# daplink_stm32f205_test.net
KiCad netlist of a schematic drawn in Altium Designer
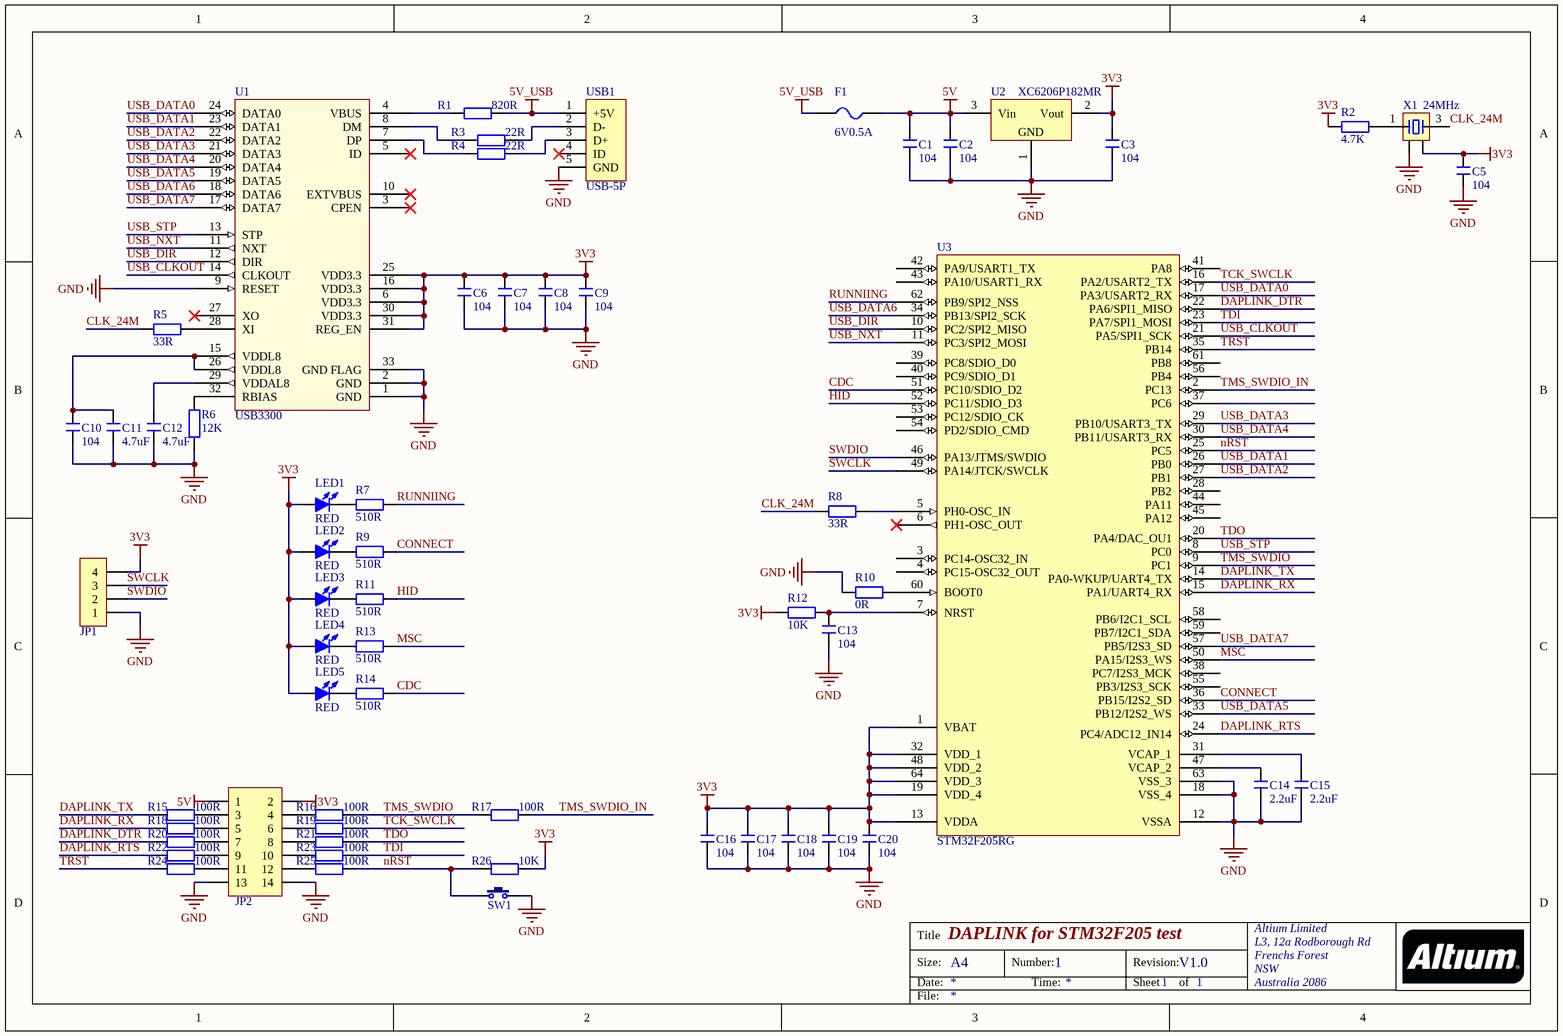
[diagram p0: daplink_stm32f205_test.SchDoc]

(export (version "E")
  (design (tool "Eeschema 10.0.6"))
  (components
    (comp (ref "C1")
      (value "104")
      (footprint "C 0603")
      (description "无极性贴片电容")
      (fields (field (name "版权归属") "源创客"))
      (libsource (lib "daplink") (part "C"))
    )
    (comp (ref "C2")
      (value "104")
      (footprint "C 0805")
      (description "无极性贴片电容")
      (fields (field (name "版权归属") "源创客"))
      (libsource (lib "daplink") (part "C"))
    )
    (comp (ref "C3")
      (value "104")
      (footprint "C 0603")
      (description "无极性贴片电容")
      (fields (field (name "版权归属") "源创客"))
      (libsource (lib "daplink") (part "C"))
    )
    (comp (ref "C5")
      (value "104")
      (footprint "C 0603")
      (description "无极性贴片电容")
      (fields (field (name "版权归属") "源创客"))
      (libsource (lib "daplink") (part "C"))
    )
    (comp (ref "C6")
      (value "104")
      (footprint "C 0603")
      (description "无极性贴片电容")
      (fields (field (name "版权归属") "源创客"))
      (libsource (lib "daplink") (part "C"))
    )
    (comp (ref "C7")
      (value "104")
      (footprint "C 0603")
      (description "无极性贴片电容")
      (fields (field (name "版权归属") "源创客"))
      (libsource (lib "daplink") (part "C"))
    )
    (comp (ref "C8")
      (value "104")
      (footprint "C 0603")
      (description "无极性贴片电容")
      (fields (field (name "版权归属") "源创客"))
      (libsource (lib "daplink") (part "C"))
    )
    (comp (ref "C9")
      (value "104")
      (footprint "C 0603")
      (description "无极性贴片电容")
      (fields (field (name "版权归属") "源创客"))
      (libsource (lib "daplink") (part "C"))
    )
    (comp (ref "C10")
      (value "104")
      (footprint "C 0603")
      (description "无极性贴片电容")
      (fields (field (name "版权归属") "源创客"))
      (libsource (lib "daplink") (part "C"))
    )
    (comp (ref "C11")
      (value "4.7uF")
      (footprint "C 0603")
      (description "无极性贴片电容")
      (fields (field (name "版权归属") "源创客"))
      (libsource (lib "daplink") (part "C"))
    )
    (comp (ref "C12")
      (value "4.7uF")
      (footprint "C 0603")
      (description "无极性贴片电容")
      (fields (field (name "版权归属") "源创客"))
      (libsource (lib "daplink") (part "C"))
    )
    (comp (ref "C13")
      (value "104")
      (footprint "C 0603")
      (description "无极性贴片电容")
      (fields (field (name "版权归属") "源创客"))
      (libsource (lib "daplink") (part "C"))
    )
    (comp (ref "C14")
      (value "2.2uF")
      (footprint "C 0603")
      (description "无极性贴片电容")
      (fields (field (name "版权归属") "源创客"))
      (libsource (lib "daplink") (part "C"))
    )
    (comp (ref "C15")
      (value "2.2uF")
      (footprint "C 0603")
      (description "无极性贴片电容")
      (fields (field (name "版权归属") "源创客"))
      (libsource (lib "daplink") (part "C"))
    )
    (comp (ref "C16")
      (value "104")
      (footprint "C 0603")
      (description "无极性贴片电容")
      (fields (field (name "版权归属") "源创客"))
      (libsource (lib "daplink") (part "C"))
    )
    (comp (ref "C17")
      (value "104")
      (footprint "C 0603")
      (description "无极性贴片电容")
      (fields (field (name "版权归属") "源创客"))
      (libsource (lib "daplink") (part "C"))
    )
    (comp (ref "C18")
      (value "104")
      (footprint "C 0603")
      (description "无极性贴片电容")
      (fields (field (name "版权归属") "源创客"))
      (libsource (lib "daplink") (part "C"))
    )
    (comp (ref "C19")
      (value "104")
      (footprint "C 0603")
      (description "无极性贴片电容")
      (fields (field (name "版权归属") "源创客"))
      (libsource (lib "daplink") (part "C"))
    )
    (comp (ref "C20")
      (value "104")
      (footprint "C 0603")
      (description "无极性贴片电容")
      (fields (field (name "版权归属") "源创客"))
      (libsource (lib "daplink") (part "C"))
    )
    (comp (ref "F1")
      (value "6V0.5A")
      (footprint "FU 0805")
      (description "贴片保险丝")
      (fields (field (name "版权归属") "源创客"))
      (libsource (lib "daplink") (part "FU"))
    )
    (comp (ref "JP1")
      (value "HDR-1X4")
      (footprint "HDR-1X4")
      (description "4P接插件")
      (fields (field (name "版权归属") "源创客"))
      (libsource (lib "daplink") (part "Header 4"))
    )
    (comp (ref "JP2")
      (value "Header 2X7")
      (footprint "HDR-7X2_H")
      (description "7*2P接插件")
      (fields (field (name "版权归属") "源创客"))
      (libsource (lib "接插件") (part "Header 7X2"))
    )
    (comp (ref "LED1")
      (value "RED")
      (footprint "LED 0805B")
      (description "贴片LED")
      (fields (field (name "版权归属") "源创客"))
      (libsource (lib "daplink") (part "LED-SMD"))
    )
    (comp (ref "LED2")
      (value "RED")
      (footprint "LED 0805B")
      (description "贴片LED")
      (fields (field (name "版权归属") "源创客"))
      (libsource (lib "daplink") (part "LED-SMD"))
    )
    (comp (ref "LED3")
      (value "RED")
      (footprint "LED 0805B")
      (description "贴片LED")
      (fields (field (name "版权归属") "源创客"))
      (libsource (lib "daplink") (part "LED-SMD"))
    )
    (comp (ref "LED4")
      (value "RED")
      (footprint "LED 0805B")
      (description "贴片LED")
      (fields (field (name "版权归属") "源创客"))
      (libsource (lib "daplink") (part "LED-SMD"))
    )
    (comp (ref "LED5")
      (value "RED")
      (footprint "LED 0805B")
      (description "贴片LED")
      (fields (field (name "版权归属") "源创客"))
      (libsource (lib "daplink") (part "LED-SMD"))
    )
    (comp (ref "R1")
      (value "820R")
      (footprint "R 0603")
      (description "贴片电阻")
      (fields (field (name "版权归属") "源创客"))
      (libsource (lib "daplink") (part "R"))
    )
    (comp (ref "R2")
      (value "4.7K")
      (footprint "R 0603")
      (description "贴片电阻")
      (fields (field (name "版权归属") "源创客"))
      (libsource (lib "daplink") (part "R"))
    )
    (comp (ref "R3")
      (value "22R")
      (footprint "R 0603")
      (description "贴片电阻")
      (fields (field (name "版权归属") "源创客"))
      (libsource (lib "daplink") (part "R"))
    )
    (comp (ref "R4")
      (value "22R")
      (footprint "R 0603")
      (description "贴片电阻")
      (fields (field (name "版权归属") "源创客"))
      (libsource (lib "daplink") (part "R"))
    )
    (comp (ref "R5")
      (value "33R")
      (footprint "R 0603")
      (description "贴片电阻")
      (fields (field (name "版权归属") "源创客"))
      (libsource (lib "daplink") (part "R"))
    )
    (comp (ref "R6")
      (value "12K")
      (footprint "R 0603")
      (description "贴片电阻")
      (fields (field (name "版权归属") "源创客"))
      (libsource (lib "daplink") (part "R"))
    )
    (comp (ref "R7")
      (value "510R")
      (footprint "R 0603")
      (description "贴片电阻")
      (fields (field (name "版权归属") "源创客"))
      (libsource (lib "daplink") (part "R"))
    )
    (comp (ref "R8")
      (value "33R")
      (footprint "R 0603")
      (description "贴片电阻")
      (fields (field (name "版权归属") "源创客"))
      (libsource (lib "daplink") (part "R"))
    )
    (comp (ref "R9")
      (value "510R")
      (footprint "R 0603")
      (description "贴片电阻")
      (fields (field (name "版权归属") "源创客"))
      (libsource (lib "daplink") (part "R"))
    )
    (comp (ref "R10")
      (value "0R")
      (footprint "R 0603")
      (description "贴片电阻")
      (fields (field (name "版权归属") "源创客"))
      (libsource (lib "daplink") (part "R"))
    )
    (comp (ref "R11")
      (value "510R")
      (footprint "R 0603")
      (description "贴片电阻")
      (fields (field (name "版权归属") "源创客"))
      (libsource (lib "daplink") (part "R"))
    )
    (comp (ref "R12")
      (value "10K")
      (footprint "R 0603")
      (description "贴片电阻")
      (fields (field (name "版权归属") "源创客"))
      (libsource (lib "daplink") (part "R"))
    )
    (comp (ref "R13")
      (value "510R")
      (footprint "R 0603")
      (description "贴片电阻")
      (fields (field (name "版权归属") "源创客"))
      (libsource (lib "daplink") (part "R"))
    )
    (comp (ref "R14")
      (value "510R")
      (footprint "R 0603")
      (description "贴片电阻")
      (fields (field (name "版权归属") "源创客"))
      (libsource (lib "daplink") (part "R"))
    )
    (comp (ref "R15")
      (value "100R")
      (footprint "R 0603")
      (description "贴片电阻")
      (fields (field (name "版权归属") "源创客"))
      (libsource (lib "daplink") (part "R"))
    )
    (comp (ref "R16")
      (value "100R")
      (footprint "R 0603")
      (description "贴片电阻")
      (fields (field (name "版权归属") "源创客"))
      (libsource (lib "daplink") (part "R"))
    )
    (comp (ref "R17")
      (value "100R")
      (footprint "R 0603")
      (description "贴片电阻")
      (fields (field (name "版权归属") "源创客"))
      (libsource (lib "daplink") (part "R"))
    )
    (comp (ref "R18")
      (value "100R")
      (footprint "R 0603")
      (description "贴片电阻")
      (fields (field (name "版权归属") "源创客"))
      (libsource (lib "daplink") (part "R"))
    )
    (comp (ref "R19")
      (value "100R")
      (footprint "R 0603")
      (description "贴片电阻")
      (fields (field (name "版权归属") "源创客"))
      (libsource (lib "daplink") (part "R"))
    )
    (comp (ref "R20")
      (value "100R")
      (footprint "R 0603")
      (description "贴片电阻")
      (fields (field (name "版权归属") "源创客"))
      (libsource (lib "daplink") (part "R"))
    )
    (comp (ref "R21")
      (value "100R")
      (footprint "R 0603")
      (description "贴片电阻")
      (fields (field (name "版权归属") "源创客"))
      (libsource (lib "daplink") (part "R"))
    )
    (comp (ref "R22")
      (value "100R")
      (footprint "R 0603")
      (description "贴片电阻")
      (fields (field (name "版权归属") "源创客"))
      (libsource (lib "daplink") (part "R"))
    )
    (comp (ref "R23")
      (value "100R")
      (footprint "R 0603")
      (description "贴片电阻")
      (fields (field (name "版权归属") "源创客"))
      (libsource (lib "daplink") (part "R"))
    )
    (comp (ref "R24")
      (value "100R")
      (footprint "R 0603")
      (description "贴片电阻")
      (fields (field (name "版权归属") "源创客"))
      (libsource (lib "daplink") (part "R"))
    )
    (comp (ref "R25")
      (value "100R")
      (footprint "R 0603")
      (description "贴片电阻")
      (fields (field (name "版权归属") "源创客"))
      (libsource (lib "daplink") (part "R"))
    )
    (comp (ref "R26")
      (value "10K")
      (footprint "R 0603")
      (description "贴片电阻")
      (fields (field (name "版权归属") "源创客"))
      (libsource (lib "daplink") (part "R"))
    )
    (comp (ref "SW1")
      (value "3x6x5")
      (footprint "TSW 3*6*4.3-S-W")
      (description "3x6轻触开关")
      (fields (field (name "版权归属") "源创客"))
      (libsource (lib "按键-开关") (part "TSW 3x6"))
    )
    (comp (ref "U1")
      (value "USB3300")
      (footprint "QFN32 5x5_N")
      (description "USB PHY")
      (libsource (lib "daplink") (part "USB3300"))
    )
    (comp (ref "U2")
      (value "XC6206P182MR")
      (footprint "SOT23-3N")
      (description "三端稳压芯片")
      (libsource (lib "daplink") (part "XC6206P182MR"))
    )
    (comp (ref "U3")
      (value "STM32F205RG")
      (footprint "LQFP64 10X10_N")
      (description "32位STM单片机")
      (fields (field (name "版权归属") "源创客"))
      (libsource (lib "daplink") (part "STM32F205RG"))
    )
    (comp (ref "USB1")
      (value "USB-5P")
      (footprint "micro usb")
      (description "微型USB母座")
      (fields (field (name "版权归属") "源创客"))
      (libsource (lib "daplink") (part "USB-5P"))
    )
    (comp (ref "X1")
      (value "24MHz")
      (footprint "XTAL-5032")
      (description "4脚晶振")
      (fields (field (name "版权归属") "源创客"))
      (libsource (lib "daplink") (part "XTAL-4"))
    )
  )
  (nets
    (net (code "1") (name "/CDC") (class "Default")
      (node (ref "R14") (pin "1") (pinfunction "1_1") (pintype "passive"))
      (node (ref "U3") (pin "51") (pinfunction "PC10/SDIO_D2_51") (pintype "bidirectional"))
    )
    (net (code "2") (name "/CLK_24M") (class "Default")
      (node (ref "R5") (pin "1") (pinfunction "1_1") (pintype "passive"))
      (node (ref "R8") (pin "1") (pinfunction "1_1") (pintype "passive"))
      (node (ref "X1") (pin "3") (pinfunction "3_3") (pintype "passive"))
    )
    (net (code "3") (name "/CONNECT") (class "Default")
      (node (ref "R9") (pin "1") (pinfunction "1_1") (pintype "passive"))
      (node (ref "U3") (pin "36") (pinfunction "PB15/I2S2_SD_36") (pintype "bidirectional"))
    )
    (net (code "4") (name "/DAPLINK_DTR") (class "Default")
      (node (ref "R20") (pin "1") (pinfunction "1_1") (pintype "passive"))
      (node (ref "U3") (pin "22") (pinfunction "PA6/SPI1_MISO_22") (pintype "bidirectional"))
    )
    (net (code "5") (name "/DAPLINK_RTS") (class "Default")
      (node (ref "R22") (pin "1") (pinfunction "1_1") (pintype "passive"))
      (node (ref "U3") (pin "24") (pinfunction "PC4/ADC12_IN14_24") (pintype "bidirectional"))
    )
    (net (code "6") (name "/DAPLINK_RX") (class "Default")
      (node (ref "R18") (pin "1") (pinfunction "1_1") (pintype "passive"))
      (node (ref "U3") (pin "15") (pinfunction "PA1/UART4_RX_15") (pintype "bidirectional"))
    )
    (net (code "7") (name "/DAPLINK_TX") (class "Default")
      (node (ref "R15") (pin "1") (pinfunction "1_1") (pintype "passive"))
      (node (ref "U3") (pin "14") (pinfunction "PA0-WKUP/UART4_TX_14") (pintype "bidirectional"))
    )
    (net (code "8") (name "/HID") (class "Default")
      (node (ref "R11") (pin "1") (pinfunction "1_1") (pintype "passive"))
      (node (ref "U3") (pin "52") (pinfunction "PC11/SDIO_D3_52") (pintype "bidirectional"))
    )
    (net (code "9") (name "/MSC") (class "Default")
      (node (ref "R13") (pin "1") (pinfunction "1_1") (pintype "passive"))
      (node (ref "U3") (pin "50") (pinfunction "PA15/I2S3_WS_50") (pintype "bidirectional"))
    )
    (net (code "10") (name "/RUNNIING") (class "Default")
      (node (ref "R7") (pin "1") (pinfunction "1_1") (pintype "passive"))
      (node (ref "U3") (pin "62") (pinfunction "PB9/SPI2_NSS_62") (pintype "bidirectional"))
    )
    (net (code "11") (name "/SWCLK") (class "Default")
      (node (ref "JP1") (pin "3") (pinfunction "3_3") (pintype "passive"))
      (node (ref "U3") (pin "49") (pinfunction "PA14/JTCK/SWCLK_49") (pintype "bidirectional"))
    )
    (net (code "12") (name "/SWDIO") (class "Default")
      (node (ref "JP1") (pin "2") (pinfunction "2_2") (pintype "passive"))
      (node (ref "U3") (pin "46") (pinfunction "PA13/JTMS/SWDIO_46") (pintype "bidirectional"))
    )
    (net (code "13") (name "/TCK_SWCLK") (class "Default")
      (node (ref "R19") (pin "2") (pinfunction "2_2") (pintype "passive"))
      (node (ref "U3") (pin "16") (pinfunction "PA2/USART2_TX_16") (pintype "bidirectional"))
    )
    (net (code "14") (name "/TDI") (class "Default")
      (node (ref "R23") (pin "2") (pinfunction "2_2") (pintype "passive"))
      (node (ref "U3") (pin "23") (pinfunction "PA7/SPI1_MOSI_23") (pintype "bidirectional"))
    )
    (net (code "15") (name "/TDO") (class "Default")
      (node (ref "R21") (pin "2") (pinfunction "2_2") (pintype "passive"))
      (node (ref "U3") (pin "20") (pinfunction "PA4/DAC_OU1_20") (pintype "bidirectional"))
    )
    (net (code "16") (name "/TMS_SWDIO") (class "Default")
      (node (ref "R16") (pin "2") (pinfunction "2_2") (pintype "passive"))
      (node (ref "R17") (pin "1") (pinfunction "1_1") (pintype "passive"))
      (node (ref "U3") (pin "9") (pinfunction "PC1_9") (pintype "bidirectional"))
    )
    (net (code "17") (name "/TMS_SWDIO_IN") (class "Default")
      (node (ref "R17") (pin "2") (pinfunction "2_2") (pintype "passive"))
      (node (ref "U3") (pin "2") (pinfunction "PC13_2") (pintype "bidirectional"))
    )
    (net (code "18") (name "/TRST") (class "Default")
      (node (ref "R24") (pin "1") (pinfunction "1_1") (pintype "passive"))
      (node (ref "U3") (pin "35") (pinfunction "PB14_35") (pintype "bidirectional"))
    )
    (net (code "19") (name "/USB_CLKOUT") (class "Default")
      (node (ref "U1") (pin "14") (pinfunction "CLKOUT_14") (pintype "output"))
      (node (ref "U3") (pin "21") (pinfunction "PA5/SPI1_SCK_21") (pintype "bidirectional"))
    )
    (net (code "20") (name "/USB_DATA0") (class "Default")
      (node (ref "U1") (pin "24") (pinfunction "DATA0_24") (pintype "bidirectional"))
      (node (ref "U3") (pin "17") (pinfunction "PA3/USART2_RX_17") (pintype "bidirectional"))
    )
    (net (code "21") (name "/USB_DATA1") (class "Default")
      (node (ref "U1") (pin "23") (pinfunction "DATA1_23") (pintype "bidirectional"))
      (node (ref "U3") (pin "26") (pinfunction "PB0_26") (pintype "bidirectional"))
    )
    (net (code "22") (name "/USB_DATA2") (class "Default")
      (node (ref "U1") (pin "22") (pinfunction "DATA2_22") (pintype "bidirectional"))
      (node (ref "U3") (pin "27") (pinfunction "PB1_27") (pintype "bidirectional"))
    )
    (net (code "23") (name "/USB_DATA3") (class "Default")
      (node (ref "U1") (pin "21") (pinfunction "DATA3_21") (pintype "bidirectional"))
      (node (ref "U3") (pin "29") (pinfunction "PB10/USART3_TX_29") (pintype "bidirectional"))
    )
    (net (code "24") (name "/USB_DATA4") (class "Default")
      (node (ref "U1") (pin "20") (pinfunction "DATA4_20") (pintype "bidirectional"))
      (node (ref "U3") (pin "30") (pinfunction "PB11/USART3_RX_30") (pintype "bidirectional"))
    )
    (net (code "25") (name "/USB_DATA5") (class "Default")
      (node (ref "U1") (pin "19") (pinfunction "DATA5_19") (pintype "bidirectional"))
      (node (ref "U3") (pin "33") (pinfunction "PB12/I2S2_WS_33") (pintype "bidirectional"))
    )
    (net (code "26") (name "/USB_DATA6") (class "Default")
      (node (ref "U1") (pin "18") (pinfunction "DATA6_18") (pintype "bidirectional"))
      (node (ref "U3") (pin "34") (pinfunction "PB13/SPI2_SCK_34") (pintype "bidirectional"))
    )
    (net (code "27") (name "/USB_DATA7") (class "Default")
      (node (ref "U1") (pin "17") (pinfunction "DATA7_17") (pintype "bidirectional"))
      (node (ref "U3") (pin "57") (pinfunction "PB5/I2S3_SD_57") (pintype "bidirectional"))
    )
    (net (code "28") (name "/USB_DIR") (class "Default")
      (node (ref "U1") (pin "12") (pinfunction "DIR_12") (pintype "output"))
      (node (ref "U3") (pin "10") (pinfunction "PC2/SPI2_MISO_10") (pintype "bidirectional"))
    )
    (net (code "29") (name "/USB_NXT") (class "Default")
      (node (ref "U1") (pin "11") (pinfunction "NXT_11") (pintype "output"))
      (node (ref "U3") (pin "11") (pinfunction "PC3/SPI2_MOSI_11") (pintype "bidirectional"))
    )
    (net (code "30") (name "/USB_STP") (class "Default")
      (node (ref "U1") (pin "13") (pinfunction "STP_13") (pintype "input"))
      (node (ref "U3") (pin "8") (pinfunction "PC0_8") (pintype "bidirectional"))
    )
    (net (code "31") (name "/nRST") (class "Default")
      (node (ref "R25") (pin "2") (pinfunction "2_2") (pintype "passive"))
      (node (ref "R26") (pin "1") (pinfunction "1_1") (pintype "passive"))
      (node (ref "SW1") (pin "1") (pinfunction "1_1") (pintype "passive"))
      (node (ref "U3") (pin "25") (pinfunction "PC5_25") (pintype "bidirectional"))
    )
    (net (code "32") (name "3V3") (class "Default")
      (node (ref "C16") (pin "2") (pinfunction "2_2") (pintype "passive"))
      (node (ref "C17") (pin "2") (pinfunction "2_2") (pintype "passive"))
      (node (ref "C18") (pin "2") (pinfunction "2_2") (pintype "passive"))
      (node (ref "C19") (pin "2") (pinfunction "2_2") (pintype "passive"))
      (node (ref "C20") (pin "2") (pinfunction "2_2") (pintype "passive"))
      (node (ref "C3") (pin "2") (pinfunction "2_2") (pintype "passive"))
      (node (ref "C5") (pin "2") (pinfunction "2_2") (pintype "passive"))
      (node (ref "C6") (pin "2") (pinfunction "2_2") (pintype "passive"))
      (node (ref "C7") (pin "2") (pinfunction "2_2") (pintype "passive"))
      (node (ref "C8") (pin "2") (pinfunction "2_2") (pintype "passive"))
      (node (ref "C9") (pin "2") (pinfunction "2_2") (pintype "passive"))
      (node (ref "JP1") (pin "4") (pinfunction "4_4") (pintype "passive"))
      (node (ref "JP2") (pin "2") (pinfunction "2_2") (pintype "passive"))
      (node (ref "LED1") (pin "1") (pinfunction "A_1") (pintype "passive"))
      (node (ref "LED2") (pin "1") (pinfunction "A_1") (pintype "passive"))
      (node (ref "LED3") (pin "1") (pinfunction "A_1") (pintype "passive"))
      (node (ref "LED4") (pin "1") (pinfunction "A_1") (pintype "passive"))
      (node (ref "LED5") (pin "1") (pinfunction "A_1") (pintype "passive"))
      (node (ref "R12") (pin "1") (pinfunction "1_1") (pintype "passive"))
      (node (ref "R2") (pin "1") (pinfunction "1_1") (pintype "passive"))
      (node (ref "R26") (pin "2") (pinfunction "2_2") (pintype "passive"))
      (node (ref "U1") (pin "16") (pinfunction "VDD3.3_16") (pintype "passive"))
      (node (ref "U1") (pin "25") (pinfunction "VDD3.3_25") (pintype "passive"))
      (node (ref "U1") (pin "30") (pinfunction "VDD3.3_30") (pintype "passive"))
      (node (ref "U1") (pin "31") (pinfunction "REG_EN_31") (pintype "passive"))
      (node (ref "U1") (pin "6") (pinfunction "VDD3.3_6") (pintype "passive"))
      (node (ref "U2") (pin "2") (pinfunction "Vout_2") (pintype "passive"))
      (node (ref "U3") (pin "1") (pinfunction "VBAT_1") (pintype "power_in"))
      (node (ref "U3") (pin "13") (pinfunction "VDDA_13") (pintype "power_in"))
      (node (ref "U3") (pin "19") (pinfunction "VDD_4_19") (pintype "power_in"))
      (node (ref "U3") (pin "32") (pinfunction "VDD_1_32") (pintype "power_in"))
      (node (ref "U3") (pin "48") (pinfunction "VDD_2_48") (pintype "power_in"))
      (node (ref "U3") (pin "64") (pinfunction "VDD_3_64") (pintype "power_in"))
      (node (ref "X1") (pin "4") (pinfunction "4_4") (pintype "passive"))
    )
    (net (code "33") (name "5V") (class "Default")
      (node (ref "C1") (pin "2") (pinfunction "2_2") (pintype "passive"))
      (node (ref "C2") (pin "2") (pinfunction "2_2") (pintype "passive"))
      (node (ref "F1") (pin "2") (pinfunction "2_2") (pintype "passive"))
      (node (ref "JP2") (pin "1") (pinfunction "1_1") (pintype "passive"))
      (node (ref "U2") (pin "3") (pinfunction "Vin_3") (pintype "passive"))
    )
    (net (code "34") (name "5V_USB") (class "Default")
      (node (ref "F1") (pin "1") (pinfunction "1_1") (pintype "passive"))
      (node (ref "R1") (pin "2") (pinfunction "2_2") (pintype "passive"))
      (node (ref "USB1") (pin "1") (pinfunction "+5V_1") (pintype "passive"))
    )
    (net (code "35") (name "GND") (class "Default")
      (node (ref "C1") (pin "1") (pinfunction "1_1") (pintype "passive"))
      (node (ref "C10") (pin "1") (pinfunction "1_1") (pintype "passive"))
      (node (ref "C11") (pin "1") (pinfunction "1_1") (pintype "passive"))
      (node (ref "C12") (pin "1") (pinfunction "1_1") (pintype "passive"))
      (node (ref "C13") (pin "1") (pinfunction "1_1") (pintype "passive"))
      (node (ref "C14") (pin "1") (pinfunction "1_1") (pintype "passive"))
      (node (ref "C15") (pin "1") (pinfunction "1_1") (pintype "passive"))
      (node (ref "C16") (pin "1") (pinfunction "1_1") (pintype "passive"))
      (node (ref "C17") (pin "1") (pinfunction "1_1") (pintype "passive"))
      (node (ref "C18") (pin "1") (pinfunction "1_1") (pintype "passive"))
      (node (ref "C19") (pin "1") (pinfunction "1_1") (pintype "passive"))
      (node (ref "C2") (pin "1") (pinfunction "1_1") (pintype "passive"))
      (node (ref "C20") (pin "1") (pinfunction "1_1") (pintype "passive"))
      (node (ref "C3") (pin "1") (pinfunction "1_1") (pintype "passive"))
      (node (ref "C5") (pin "1") (pinfunction "1_1") (pintype "passive"))
      (node (ref "C6") (pin "1") (pinfunction "1_1") (pintype "passive"))
      (node (ref "C7") (pin "1") (pinfunction "1_1") (pintype "passive"))
      (node (ref "C8") (pin "1") (pinfunction "1_1") (pintype "passive"))
      (node (ref "C9") (pin "1") (pinfunction "1_1") (pintype "passive"))
      (node (ref "JP1") (pin "1") (pinfunction "1_1") (pintype "passive"))
      (node (ref "JP2") (pin "13") (pinfunction "13_13") (pintype "passive"))
      (node (ref "JP2") (pin "14") (pinfunction "14_14") (pintype "passive"))
      (node (ref "R10") (pin "1") (pinfunction "1_1") (pintype "passive"))
      (node (ref "R6") (pin "1") (pinfunction "1_1") (pintype "passive"))
      (node (ref "SW1") (pin "2") (pinfunction "2_2") (pintype "passive"))
      (node (ref "U1") (pin "1") (pinfunction "GND_1") (pintype "passive"))
      (node (ref "U1") (pin "2") (pinfunction "GND_2") (pintype "passive"))
      (node (ref "U1") (pin "33") (pinfunction "GND_FLAG_33") (pintype "passive"))
      (node (ref "U1") (pin "9") (pinfunction "RESET_9") (pintype "input"))
      (node (ref "U2") (pin "1") (pinfunction "GND_1") (pintype "passive"))
      (node (ref "U3") (pin "12") (pinfunction "VSSA_12") (pintype "power_in"))
      (node (ref "U3") (pin "18") (pinfunction "VSS_4_18") (pintype "power_in"))
      (node (ref "U3") (pin "63") (pinfunction "VSS_3_63") (pintype "power_in"))
      (node (ref "USB1") (pin "5") (pinfunction "GND_5") (pintype "passive"))
      (node (ref "X1") (pin "2") (pinfunction "2_2") (pintype "passive"))
    )
    (net (code "36") (name "Net-(C10-Pad2)") (class "Default")
      (node (ref "C10") (pin "2") (pinfunction "2_2") (pintype "passive"))
      (node (ref "C11") (pin "2") (pinfunction "2_2") (pintype "passive"))
      (node (ref "U1") (pin "15") (pinfunction "VDDL8_15") (pintype "output"))
      (node (ref "U1") (pin "26") (pinfunction "VDDL8_26") (pintype "output"))
    )
    (net (code "37") (name "Net-(JP2-Pad3)") (class "Default")
      (node (ref "JP2") (pin "3") (pinfunction "3_3") (pintype "passive"))
      (node (ref "R15") (pin "2") (pinfunction "2_2") (pintype "passive"))
    )
    (net (code "38") (name "Net-(JP2-Pad4)") (class "Default")
      (node (ref "JP2") (pin "4") (pinfunction "4_4") (pintype "passive"))
      (node (ref "R16") (pin "1") (pinfunction "1_1") (pintype "passive"))
    )
    (net (code "39") (name "Net-(JP2-Pad5)") (class "Default")
      (node (ref "JP2") (pin "5") (pinfunction "5_5") (pintype "passive"))
      (node (ref "R18") (pin "2") (pinfunction "2_2") (pintype "passive"))
    )
    (net (code "40") (name "Net-(JP2-Pad6)") (class "Default")
      (node (ref "JP2") (pin "6") (pinfunction "6_6") (pintype "passive"))
      (node (ref "R19") (pin "1") (pinfunction "1_1") (pintype "passive"))
    )
    (net (code "41") (name "Net-(JP2-Pad7)") (class "Default")
      (node (ref "JP2") (pin "7") (pinfunction "7_7") (pintype "passive"))
      (node (ref "R20") (pin "2") (pinfunction "2_2") (pintype "passive"))
    )
    (net (code "42") (name "Net-(JP2-Pad8)") (class "Default")
      (node (ref "JP2") (pin "8") (pinfunction "8_8") (pintype "passive"))
      (node (ref "R21") (pin "1") (pinfunction "1_1") (pintype "passive"))
    )
    (net (code "43") (name "Net-(JP2-Pad9)") (class "Default")
      (node (ref "JP2") (pin "9") (pinfunction "9_9") (pintype "passive"))
      (node (ref "R22") (pin "2") (pinfunction "2_2") (pintype "passive"))
    )
    (net (code "44") (name "Net-(JP2-Pad10)") (class "Default")
      (node (ref "JP2") (pin "10") (pinfunction "10_10") (pintype "passive"))
      (node (ref "R23") (pin "1") (pinfunction "1_1") (pintype "passive"))
    )
    (net (code "45") (name "Net-(JP2-Pad11)") (class "Default")
      (node (ref "JP2") (pin "11") (pinfunction "11_11") (pintype "passive"))
      (node (ref "R24") (pin "2") (pinfunction "2_2") (pintype "passive"))
    )
    (net (code "46") (name "Net-(JP2-Pad12)") (class "Default")
      (node (ref "JP2") (pin "12") (pinfunction "12_12") (pintype "passive"))
      (node (ref "R25") (pin "1") (pinfunction "1_1") (pintype "passive"))
    )
    (net (code "47") (name "Net-(LED1-K)") (class "Default")
      (node (ref "LED1") (pin "2") (pinfunction "K_2") (pintype "passive"))
      (node (ref "R7") (pin "2") (pinfunction "2_2") (pintype "passive"))
    )
    (net (code "48") (name "Net-(LED2-K)") (class "Default")
      (node (ref "LED2") (pin "2") (pinfunction "K_2") (pintype "passive"))
      (node (ref "R9") (pin "2") (pinfunction "2_2") (pintype "passive"))
    )
    (net (code "49") (name "Net-(LED3-K)") (class "Default")
      (node (ref "LED3") (pin "2") (pinfunction "K_2") (pintype "passive"))
      (node (ref "R11") (pin "2") (pinfunction "2_2") (pintype "passive"))
    )
    (net (code "50") (name "Net-(LED4-K)") (class "Default")
      (node (ref "LED4") (pin "2") (pinfunction "K_2") (pintype "passive"))
      (node (ref "R13") (pin "2") (pinfunction "2_2") (pintype "passive"))
    )
    (net (code "51") (name "Net-(LED5-K)") (class "Default")
      (node (ref "LED5") (pin "2") (pinfunction "K_2") (pintype "passive"))
      (node (ref "R14") (pin "2") (pinfunction "2_2") (pintype "passive"))
    )
    (net (code "52") (name "Net-(R2-Pad2)") (class "Default")
      (node (ref "R2") (pin "2") (pinfunction "2_2") (pintype "passive"))
      (node (ref "X1") (pin "1") (pinfunction "1_1") (pintype "passive"))
    )
    (net (code "53") (name "Net-(U1-DM)") (class "Default")
      (node (ref "R3") (pin "1") (pinfunction "1_1") (pintype "passive"))
      (node (ref "U1") (pin "8") (pinfunction "DM_8") (pintype "passive"))
    )
    (net (code "54") (name "Net-(U1-DP)") (class "Default")
      (node (ref "R4") (pin "1") (pinfunction "1_1") (pintype "passive"))
      (node (ref "U1") (pin "7") (pinfunction "DP_7") (pintype "passive"))
    )
    (net (code "55") (name "Net-(U1-RBIAS)") (class "Default")
      (node (ref "R6") (pin "2") (pinfunction "2_2") (pintype "passive"))
      (node (ref "U1") (pin "32") (pinfunction "RBIAS_32") (pintype "passive"))
    )
    (net (code "56") (name "Net-(U1-VBUS)") (class "Default")
      (node (ref "R1") (pin "1") (pinfunction "1_1") (pintype "passive"))
      (node (ref "U1") (pin "4") (pinfunction "VBUS_4") (pintype "passive"))
    )
    (net (code "57") (name "Net-(U1-VDDAL8)") (class "Default")
      (node (ref "C12") (pin "2") (pinfunction "2_2") (pintype "passive"))
      (node (ref "U1") (pin "29") (pinfunction "VDDAL8_29") (pintype "output"))
    )
    (net (code "58") (name "Net-(U1-XI)") (class "Default")
      (node (ref "R5") (pin "2") (pinfunction "2_2") (pintype "passive"))
      (node (ref "U1") (pin "28") (pinfunction "XI_28") (pintype "passive"))
    )
    (net (code "59") (name "Net-(U3-BOOT0)") (class "Default")
      (node (ref "R10") (pin "2") (pinfunction "2_2") (pintype "passive"))
      (node (ref "U3") (pin "60") (pinfunction "BOOT0_60") (pintype "input"))
    )
    (net (code "60") (name "Net-(U3-NRST)") (class "Default")
      (node (ref "C13") (pin "2") (pinfunction "2_2") (pintype "passive"))
      (node (ref "R12") (pin "2") (pinfunction "2_2") (pintype "passive"))
      (node (ref "U3") (pin "7") (pinfunction "NRST_7") (pintype "bidirectional"))
    )
    (net (code "61") (name "Net-(U3-PH0-OSC_IN)") (class "Default")
      (node (ref "R8") (pin "2") (pinfunction "2_2") (pintype "passive"))
      (node (ref "U3") (pin "5") (pinfunction "PH0-OSC_IN_5") (pintype "input"))
    )
    (net (code "62") (name "Net-(U3-VCAP_1)") (class "Default")
      (node (ref "C15") (pin "2") (pinfunction "2_2") (pintype "passive"))
      (node (ref "U3") (pin "31") (pinfunction "VCAP_1_31") (pintype "passive"))
    )
    (net (code "63") (name "Net-(U3-VCAP_2)") (class "Default")
      (node (ref "C14") (pin "2") (pinfunction "2_2") (pintype "passive"))
      (node (ref "U3") (pin "47") (pinfunction "VCAP_2_47") (pintype "passive"))
    )
    (net (code "64") (name "Net-(USB1-D+)") (class "Default")
      (node (ref "R4") (pin "2") (pinfunction "2_2") (pintype "passive"))
      (node (ref "USB1") (pin "3") (pinfunction "D+_3") (pintype "passive"))
    )
    (net (code "65") (name "Net-(USB1-D-)") (class "Default")
      (node (ref "R3") (pin "2") (pinfunction "2_2") (pintype "passive"))
      (node (ref "USB1") (pin "2") (pinfunction "D-_2") (pintype "passive"))
    )
    (net (code "66") (name "unconnected-(U1-CPEN-Pad3)") (class "Default")
      (node (ref "U1") (pin "3") (pinfunction "CPEN_3") (pintype "passive+no_connect"))
    )
    (net (code "67") (name "unconnected-(U1-EXTVBUS-Pad10)") (class "Default")
      (node (ref "U1") (pin "10") (pinfunction "EXTVBUS_10") (pintype "passive+no_connect"))
    )
    (net (code "68") (name "unconnected-(U1-ID-Pad5)") (class "Default")
      (node (ref "U1") (pin "5") (pinfunction "ID_5") (pintype "passive+no_connect"))
    )
    (net (code "69") (name "unconnected-(U1-XO-Pad27)") (class "Default")
      (node (ref "U1") (pin "27") (pinfunction "XO_27") (pintype "passive+no_connect"))
    )
    (net (code "70") (name "unconnected-(U3-PA8-Pad41)") (class "Default")
      (node (ref "U3") (pin "41") (pinfunction "PA8_41") (pintype "bidirectional"))
    )
    (net (code "71") (name "unconnected-(U3-PA9{slash}USART1_TX-Pad42)") (class "Default")
      (node (ref "U3") (pin "42") (pinfunction "PA9/USART1_TX_42") (pintype "bidirectional"))
    )
    (net (code "72") (name "unconnected-(U3-PA10{slash}USART1_RX-Pad43)") (class "Default")
      (node (ref "U3") (pin "43") (pinfunction "PA10/USART1_RX_43") (pintype "bidirectional"))
    )
    (net (code "73") (name "unconnected-(U3-PA11-Pad44)") (class "Default")
      (node (ref "U3") (pin "44") (pinfunction "PA11_44") (pintype "bidirectional"))
    )
    (net (code "74") (name "unconnected-(U3-PA12-Pad45)") (class "Default")
      (node (ref "U3") (pin "45") (pinfunction "PA12_45") (pintype "bidirectional"))
    )
    (net (code "75") (name "unconnected-(U3-PB2-Pad28)") (class "Default")
      (node (ref "U3") (pin "28") (pinfunction "PB2_28") (pintype "bidirectional"))
    )
    (net (code "76") (name "unconnected-(U3-PB3{slash}I2S3_SCK-Pad55)") (class "Default")
      (node (ref "U3") (pin "55") (pinfunction "PB3/I2S3_SCK_55") (pintype "bidirectional"))
    )
    (net (code "77") (name "unconnected-(U3-PB4-Pad56)") (class "Default")
      (node (ref "U3") (pin "56") (pinfunction "PB4_56") (pintype "bidirectional"))
    )
    (net (code "78") (name "unconnected-(U3-PB6{slash}I2C1_SCL-Pad58)") (class "Default")
      (node (ref "U3") (pin "58") (pinfunction "PB6/I2C1_SCL_58") (pintype "bidirectional"))
    )
    (net (code "79") (name "unconnected-(U3-PB7{slash}I2C1_SDA-Pad59)") (class "Default")
      (node (ref "U3") (pin "59") (pinfunction "PB7/I2C1_SDA_59") (pintype "bidirectional"))
    )
    (net (code "80") (name "unconnected-(U3-PB8-Pad61)") (class "Default")
      (node (ref "U3") (pin "61") (pinfunction "PB8_61") (pintype "bidirectional"))
    )
    (net (code "81") (name "unconnected-(U3-PC6-Pad37)") (class "Default")
      (node (ref "U3") (pin "37") (pinfunction "PC6_37") (pintype "bidirectional"))
    )
    (net (code "82") (name "unconnected-(U3-PC7{slash}I2S3_MCK-Pad38)") (class "Default")
      (node (ref "U3") (pin "38") (pinfunction "PC7/I2S3_MCK_38") (pintype "bidirectional"))
    )
    (net (code "83") (name "unconnected-(U3-PC8{slash}SDIO_D0-Pad39)") (class "Default")
      (node (ref "U3") (pin "39") (pinfunction "PC8/SDIO_D0_39") (pintype "bidirectional"))
    )
    (net (code "84") (name "unconnected-(U3-PC9{slash}SDIO_D1-Pad40)") (class "Default")
      (node (ref "U3") (pin "40") (pinfunction "PC9/SDIO_D1_40") (pintype "bidirectional"))
    )
    (net (code "85") (name "unconnected-(U3-PC12{slash}SDIO_CK-Pad53)") (class "Default")
      (node (ref "U3") (pin "53") (pinfunction "PC12/SDIO_CK_53") (pintype "bidirectional"))
    )
    (net (code "86") (name "unconnected-(U3-PC14-OSC32_IN-Pad3)") (class "Default")
      (node (ref "U3") (pin "3") (pinfunction "PC14-OSC32_IN_3") (pintype "bidirectional"))
    )
    (net (code "87") (name "unconnected-(U3-PC15-OSC32_OUT-Pad4)") (class "Default")
      (node (ref "U3") (pin "4") (pinfunction "PC15-OSC32_OUT_4") (pintype "bidirectional"))
    )
    (net (code "88") (name "unconnected-(U3-PD2{slash}SDIO_CMD-Pad54)") (class "Default")
      (node (ref "U3") (pin "54") (pinfunction "PD2/SDIO_CMD_54") (pintype "bidirectional"))
    )
    (net (code "89") (name "unconnected-(U3-PH1-OSC_OUT-Pad6)") (class "Default")
      (node (ref "U3") (pin "6") (pinfunction "PH1-OSC_OUT_6") (pintype "output+no_connect"))
    )
    (net (code "90") (name "unconnected-(USB1-ID-Pad4)") (class "Default")
      (node (ref "USB1") (pin "4") (pinfunction "ID_4") (pintype "passive+no_connect"))
    )
  )
)
